# tiny_rack_v2_psu_core.net
KiCad netlist of a schematic drawn in EAGLE
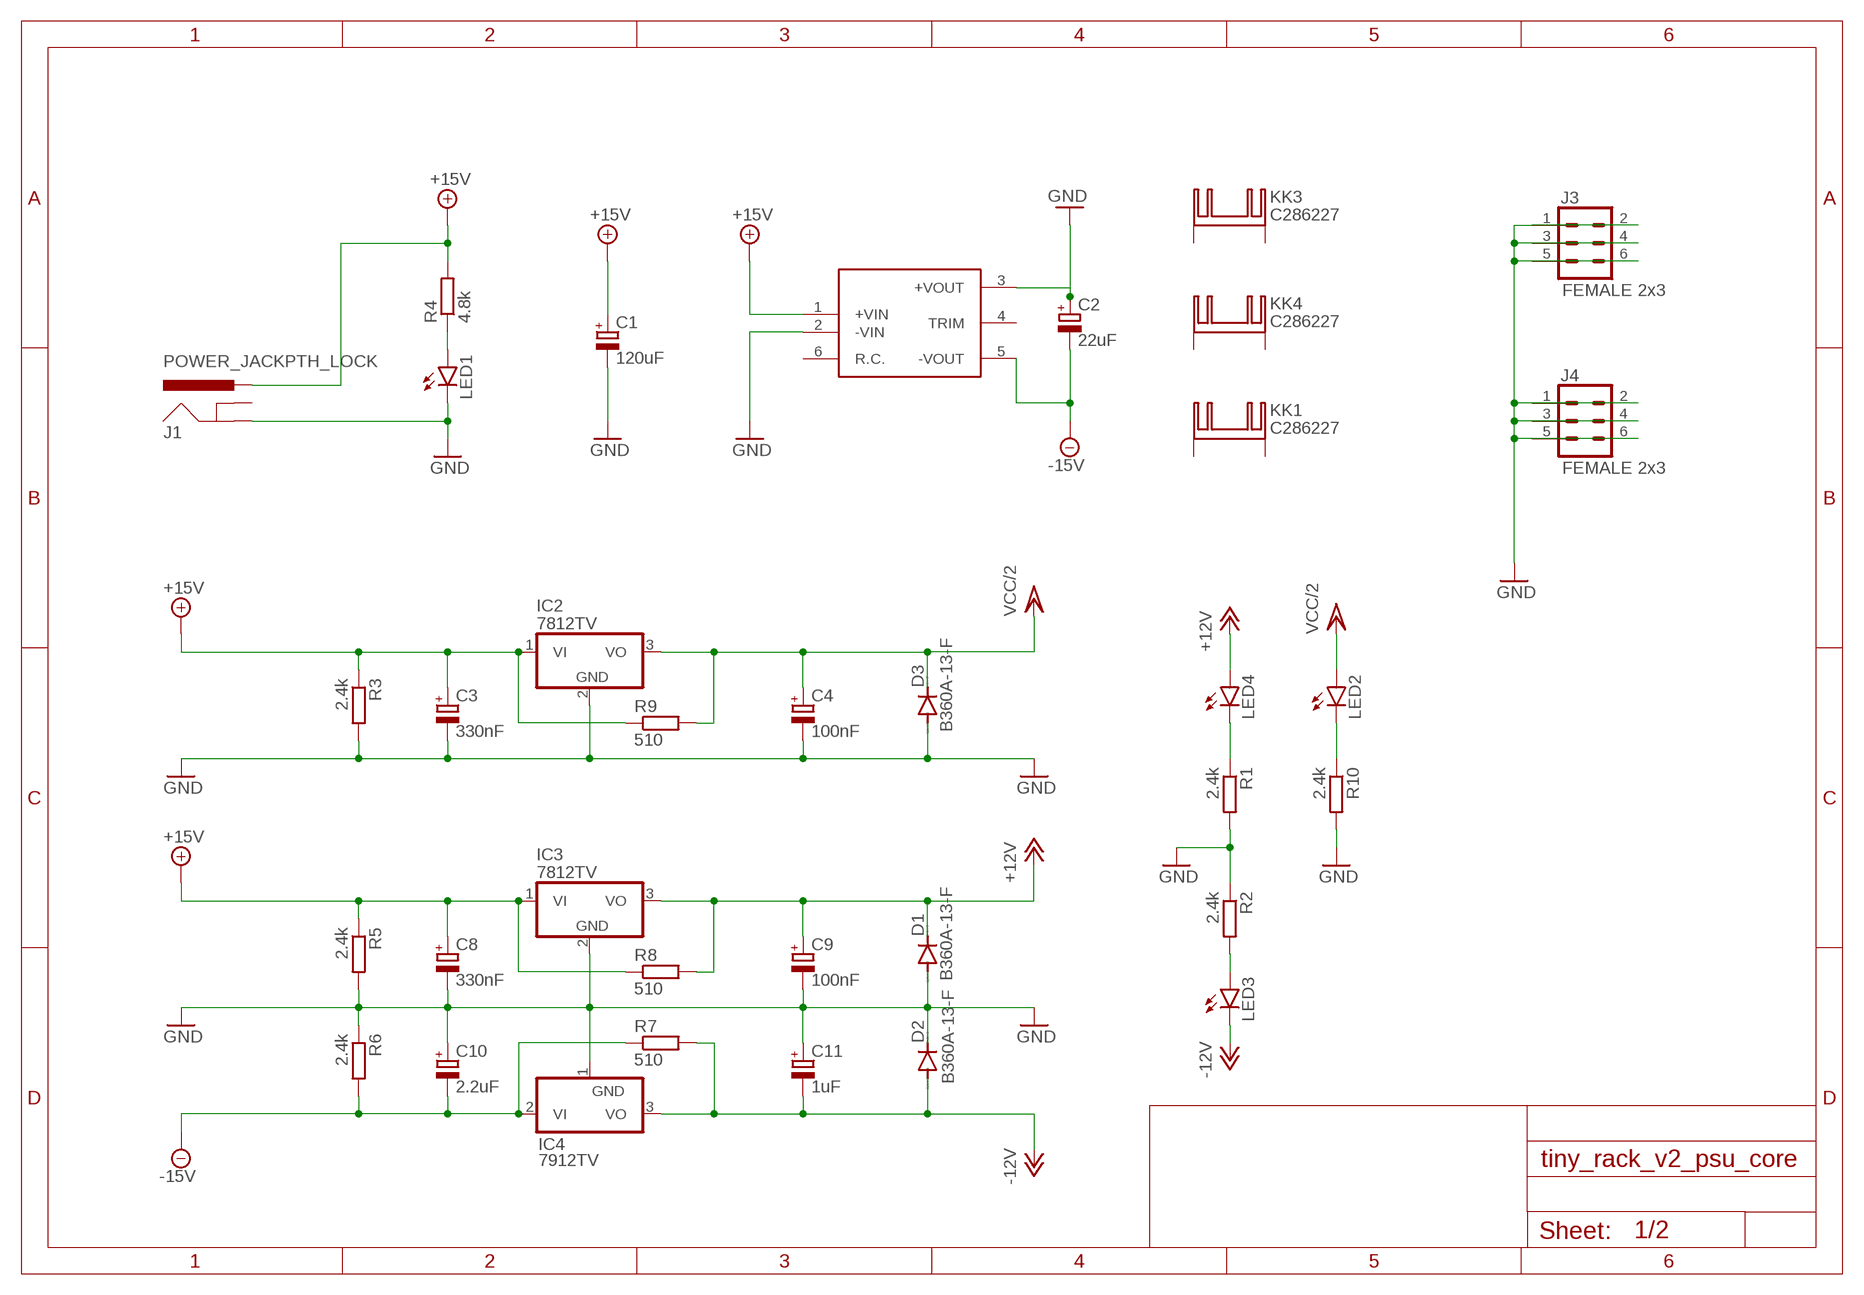
[diagram p0: schematic, sheet 1]
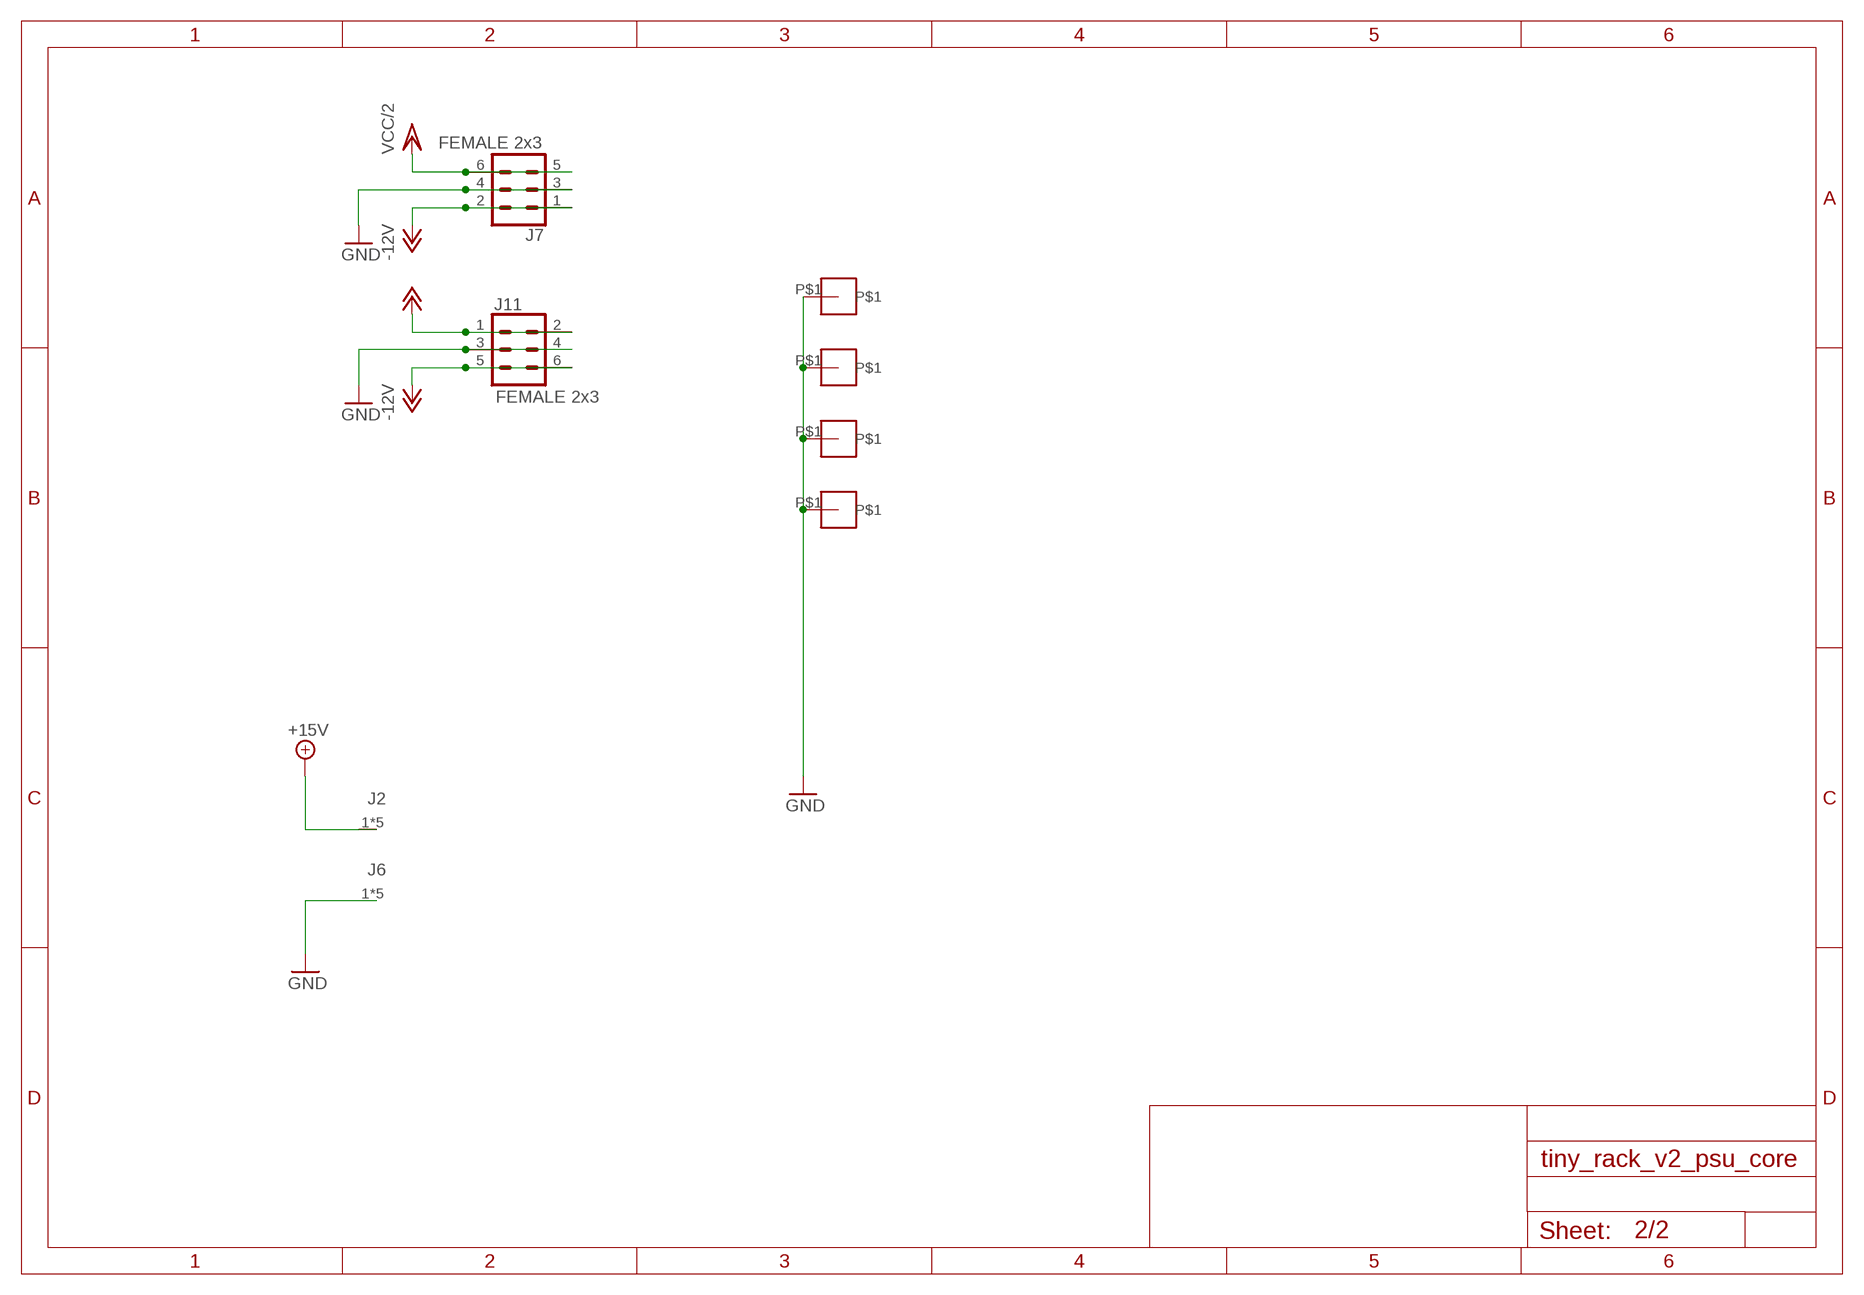
[diagram p1: schematic, sheet 2]

(export (version "E")
  (design (tool "Eeschema 10.0.6"))
  (components
    (comp (ref "J2")
      (value "30A-SCREW-CONN")
      (footprint "eagle-import:50X72")
      (libsource (lib "eagle-import") (part "30A-SCREW-CONN"))
    )
    (comp (ref "J6")
      (value "30A-SCREW-CONN")
      (footprint "eagle-import:50X72")
      (libsource (lib "eagle-import") (part "30A-SCREW-CONN"))
    )
    (comp (ref "J7")
      (value "FEMALE 2x3")
      (footprint "eagle-import:2X3")
      (libsource (lib "eagle-import") (part "CONN_03X2FEMALE"))
    )
    (comp (ref "J11")
      (value "FEMALE 2x3")
      (footprint "eagle-import:2X3")
      (libsource (lib "eagle-import") (part "CONN_03X2FEMALE"))
    )
    (comp (ref "U$3")
      (value "M3-HOLE")
      (footprint "eagle-import:M3-HOLE")
      (libsource (lib "eagle-import") (part "M3-HOLE"))
    )
    (comp (ref "U$4")
      (value "M3-HOLE")
      (footprint "eagle-import:M3-HOLE")
      (libsource (lib "eagle-import") (part "M3-HOLE"))
    )
    (comp (ref "U$5")
      (value "M3-HOLE")
      (footprint "eagle-import:M3-HOLE")
      (libsource (lib "eagle-import") (part "M3-HOLE"))
    )
    (comp (ref "U$6")
      (value "M3-HOLE")
      (footprint "eagle-import:M3-HOLE")
      (libsource (lib "eagle-import") (part "M3-HOLE"))
    )
    (comp (ref "C1")
      (value "120uF")
      (footprint "eagle-import:E5-10,5")
      (libsource (lib "eagle-import") (part "CPOL-EUE5-10.5"))
    )
    (comp (ref "C2")
      (value "22uF")
      (footprint "eagle-import:E2,5-6")
      (libsource (lib "eagle-import") (part "CPOL-EUE2.5-6"))
    )
    (comp (ref "C3")
      (value "330nF")
      (footprint "eagle-import:CAPMP3216X180N")
      (libsource (lib "eagle-import") (part "C-POLTANTALUM-1206(3216-METRIC)_"))
    )
    (comp (ref "C4")
      (value "100nF")
      (footprint "eagle-import:CAPMP3216X180N")
      (libsource (lib "eagle-import") (part "C-POLTANTALUM-1206(3216-METRIC)_"))
    )
    (comp (ref "C8")
      (value "330nF")
      (footprint "eagle-import:CAPMP3216X180N")
      (libsource (lib "eagle-import") (part "C-POLTANTALUM-1206(3216-METRIC)_"))
    )
    (comp (ref "C9")
      (value "100nF")
      (footprint "eagle-import:CAPMP3216X180N")
      (libsource (lib "eagle-import") (part "C-POLTANTALUM-1206(3216-METRIC)_"))
    )
    (comp (ref "C10")
      (value "2.2uF")
      (footprint "eagle-import:CAPMP3528X210N")
      (libsource (lib "eagle-import") (part "C-POLTANTALUM-1411(3528-METRIC)_"))
    )
    (comp (ref "C11")
      (value "1uF")
      (footprint "eagle-import:CAPMP3216X180N")
      (libsource (lib "eagle-import") (part "C-POLTANTALUM-1206(3216-METRIC)_"))
    )
    (comp (ref "D1")
      (value "B360A-13-F")
      (footprint "eagle-import:DO-214AC")
      (libsource (lib "eagle-import") (part "DIODE-DO-214AC"))
    )
    (comp (ref "D2")
      (value "B360A-13-F")
      (footprint "eagle-import:DO-214AC")
      (libsource (lib "eagle-import") (part "DIODE-DO-214AC"))
    )
    (comp (ref "D3")
      (value "B360A-13-F")
      (footprint "eagle-import:DO-214AC")
      (libsource (lib "eagle-import") (part "DIODE-DO-214AC"))
    )
    (comp (ref "IC1")
      (value "SKMW")
      (footprint "eagle-import:SKMW")
      (libsource (lib "eagle-import") (part "SKMW"))
    )
    (comp (ref "IC2")
      (value "7812TV")
      (footprint "eagle-import:TO220V")
      (libsource (lib "eagle-import") (part "78TV12"))
    )
    (comp (ref "IC3")
      (value "7812TV")
      (footprint "eagle-import:TO220V")
      (libsource (lib "eagle-import") (part "78TV12"))
    )
    (comp (ref "IC4")
      (value "7912TV")
      (footprint "eagle-import:TO220V")
      (libsource (lib "eagle-import") (part "79TV12"))
    )
    (comp (ref "J1")
      (value "POWER_JACKPTH_LOCK")
      (footprint "eagle-import:POWER_JACK_PTH_LOCK")
      (libsource (lib "eagle-import") (part "POWER_JACKPTH_LOCK"))
    )
    (comp (ref "J3")
      (value "FEMALE 2x3")
      (footprint "eagle-import:2X3")
      (libsource (lib "eagle-import") (part "CONN_03X2FEMALE"))
    )
    (comp (ref "J4")
      (value "FEMALE 2x3")
      (footprint "eagle-import:2X3")
      (libsource (lib "eagle-import") (part "CONN_03X2FEMALE"))
    )
    (comp (ref "KK1")
      (value "C286227")
      (footprint "eagle-import:C286227")
      (libsource (lib "eagle-import") (part "C286227"))
    )
    (comp (ref "KK3")
      (value "C286227")
      (footprint "eagle-import:C286227")
      (libsource (lib "eagle-import") (part "C286227"))
    )
    (comp (ref "KK4")
      (value "C286227")
      (footprint "eagle-import:C286227")
      (libsource (lib "eagle-import") (part "C286227"))
    )
    (comp (ref "LED1")
      (value "LEDCHIP-LED0805")
      (footprint "eagle-import:CHIP-LED0805")
      (libsource (lib "eagle-import") (part "LEDCHIP-LED0805"))
    )
    (comp (ref "LED2")
      (value "LEDCHIP-LED0805")
      (footprint "eagle-import:CHIP-LED0805")
      (libsource (lib "eagle-import") (part "LEDCHIP-LED0805"))
    )
    (comp (ref "LED3")
      (value "LEDCHIP-LED0805")
      (footprint "eagle-import:CHIP-LED0805")
      (libsource (lib "eagle-import") (part "LEDCHIP-LED0805"))
    )
    (comp (ref "LED4")
      (value "LEDCHIP-LED0805")
      (footprint "eagle-import:CHIP-LED0805")
      (libsource (lib "eagle-import") (part "LEDCHIP-LED0805"))
    )
    (comp (ref "R1")
      (value "2.4k")
      (footprint "eagle-import:R0805")
      (libsource (lib "eagle-import") (part "R-EU_R0805"))
    )
    (comp (ref "R2")
      (value "2.4k")
      (footprint "eagle-import:R0805")
      (libsource (lib "eagle-import") (part "R-EU_R0805"))
    )
    (comp (ref "R3")
      (value "2.4k")
      (footprint "eagle-import:R0805")
      (libsource (lib "eagle-import") (part "R-EU_R0805"))
    )
    (comp (ref "R4")
      (value "4.8k")
      (footprint "eagle-import:R0805")
      (libsource (lib "eagle-import") (part "R-EU_R0805"))
    )
    (comp (ref "R5")
      (value "2.4k")
      (footprint "eagle-import:R0805")
      (libsource (lib "eagle-import") (part "R-EU_R0805"))
    )
    (comp (ref "R6")
      (value "2.4k")
      (footprint "eagle-import:R0805")
      (libsource (lib "eagle-import") (part "R-EU_R0805"))
    )
    (comp (ref "R7")
      (value "510")
      (footprint "eagle-import:R0805")
      (libsource (lib "eagle-import") (part "R-EU_R0805"))
    )
    (comp (ref "R8")
      (value "510")
      (footprint "eagle-import:R0805")
      (libsource (lib "eagle-import") (part "R-EU_R0805"))
    )
    (comp (ref "R9")
      (value "510")
      (footprint "eagle-import:R0805")
      (libsource (lib "eagle-import") (part "R-EU_R0805"))
    )
    (comp (ref "R10")
      (value "2.4k")
      (footprint "eagle-import:R0805")
      (libsource (lib "eagle-import") (part "R-EU_R0805"))
    )
  )
  (nets
    (net (code "1") (name "+12V") (class "Default")
      (node (ref "C9") (pin "1") (pinfunction "+_1") (pintype "passive"))
      (node (ref "D1") (pin "C") (pinfunction "C_C") (pintype "passive"))
      (node (ref "IC3") (pin "3") (pinfunction "VO_3") (pintype "passive"))
      (node (ref "J11") (pin "1") (pinfunction "1_1") (pintype "bidirectional"))
      (node (ref "J11") (pin "2") (pinfunction "2_2") (pintype "bidirectional"))
      (node (ref "LED4") (pin "A") (pinfunction "A_A") (pintype "passive"))
      (node (ref "R8") (pin "2") (pinfunction "2_2") (pintype "passive"))
    )
    (net (code "2") (name "+15V") (class "Default")
      (node (ref "C1") (pin "+") (pinfunction "+_+") (pintype "passive"))
      (node (ref "C3") (pin "1") (pinfunction "+_1") (pintype "passive"))
      (node (ref "C8") (pin "1") (pinfunction "+_1") (pintype "passive"))
      (node (ref "IC1") (pin "1") (pinfunction "+VIN_1") (pintype "input"))
      (node (ref "IC2") (pin "1") (pinfunction "VI_1") (pintype "input"))
      (node (ref "IC3") (pin "1") (pinfunction "VI_1") (pintype "input"))
      (node (ref "J1") (pin "PWR") (pinfunction "PWR_PWR") (pintype "bidirectional"))
      (node (ref "J2") (pin "1") (pinfunction "2_1") (pintype "passive"))
      (node (ref "J2") (pin "2") (pinfunction "2_2") (pintype "passive"))
      (node (ref "J2") (pin "3") (pinfunction "2_3") (pintype "passive"))
      (node (ref "J2") (pin "4") (pinfunction "2_4") (pintype "passive"))
      (node (ref "J2") (pin "P$1") (pinfunction "2_P$1") (pintype "passive"))
      (node (ref "R3") (pin "1") (pinfunction "1_1") (pintype "passive"))
      (node (ref "R4") (pin "2") (pinfunction "2_2") (pintype "passive"))
      (node (ref "R5") (pin "1") (pinfunction "1_1") (pintype "passive"))
      (node (ref "R8") (pin "1") (pinfunction "1_1") (pintype "passive"))
      (node (ref "R9") (pin "1") (pinfunction "1_1") (pintype "passive"))
    )
    (net (code "3") (name "-12V") (class "Default")
      (node (ref "C11") (pin "2") (pinfunction "-_2") (pintype "passive"))
      (node (ref "D2") (pin "A") (pinfunction "A_A") (pintype "passive"))
      (node (ref "IC4") (pin "3") (pinfunction "VO_3") (pintype "passive"))
      (node (ref "J11") (pin "5") (pinfunction "5_5") (pintype "bidirectional"))
      (node (ref "J11") (pin "6") (pinfunction "6_6") (pintype "bidirectional"))
      (node (ref "J7") (pin "1") (pinfunction "1_1") (pintype "bidirectional"))
      (node (ref "J7") (pin "2") (pinfunction "2_2") (pintype "bidirectional"))
      (node (ref "LED3") (pin "C") (pinfunction "C_C") (pintype "passive"))
      (node (ref "R7") (pin "2") (pinfunction "2_2") (pintype "passive"))
    )
    (net (code "4") (name "-15V") (class "Default")
      (node (ref "C10") (pin "2") (pinfunction "-_2") (pintype "passive"))
      (node (ref "C2") (pin "-") (pinfunction "-_-") (pintype "passive"))
      (node (ref "IC1") (pin "5") (pinfunction "-VOUT_5") (pintype "output"))
      (node (ref "IC4") (pin "2") (pinfunction "VI_2") (pintype "input"))
      (node (ref "R6") (pin "2") (pinfunction "2_2") (pintype "passive"))
      (node (ref "R7") (pin "1") (pinfunction "1_1") (pintype "passive"))
    )
    (net (code "5") (name "GND") (class "Default")
      (node (ref "C1") (pin "-") (pinfunction "-_-") (pintype "passive"))
      (node (ref "C10") (pin "1") (pinfunction "+_1") (pintype "passive"))
      (node (ref "C11") (pin "1") (pinfunction "+_1") (pintype "passive"))
      (node (ref "C2") (pin "+") (pinfunction "+_+") (pintype "passive"))
      (node (ref "C3") (pin "2") (pinfunction "-_2") (pintype "passive"))
      (node (ref "C4") (pin "2") (pinfunction "-_2") (pintype "passive"))
      (node (ref "C8") (pin "2") (pinfunction "-_2") (pintype "passive"))
      (node (ref "C9") (pin "2") (pinfunction "-_2") (pintype "passive"))
      (node (ref "D1") (pin "A") (pinfunction "A_A") (pintype "passive"))
      (node (ref "D2") (pin "C") (pinfunction "C_C") (pintype "passive"))
      (node (ref "D3") (pin "A") (pinfunction "A_A") (pintype "passive"))
      (node (ref "IC1") (pin "2") (pinfunction "-VIN_2") (pintype "bidirectional"))
      (node (ref "IC1") (pin "3") (pinfunction "+VOUT_3") (pintype "output"))
      (node (ref "IC2") (pin "2") (pinfunction "GND_2") (pintype "passive"))
      (node (ref "IC3") (pin "2") (pinfunction "GND_2") (pintype "passive"))
      (node (ref "IC4") (pin "1") (pinfunction "GND_1") (pintype "passive"))
      (node (ref "J1") (pin "GND") (pinfunction "GND_GND") (pintype "bidirectional"))
      (node (ref "J11") (pin "3") (pinfunction "3_3") (pintype "bidirectional"))
      (node (ref "J11") (pin "4") (pinfunction "4_4") (pintype "bidirectional"))
      (node (ref "J3") (pin "1") (pinfunction "1_1") (pintype "bidirectional"))
      (node (ref "J3") (pin "2") (pinfunction "2_2") (pintype "bidirectional"))
      (node (ref "J3") (pin "3") (pinfunction "3_3") (pintype "bidirectional"))
      (node (ref "J3") (pin "4") (pinfunction "4_4") (pintype "bidirectional"))
      (node (ref "J3") (pin "5") (pinfunction "5_5") (pintype "bidirectional"))
      (node (ref "J3") (pin "6") (pinfunction "6_6") (pintype "bidirectional"))
      (node (ref "J4") (pin "1") (pinfunction "1_1") (pintype "bidirectional"))
      (node (ref "J4") (pin "2") (pinfunction "2_2") (pintype "bidirectional"))
      (node (ref "J4") (pin "3") (pinfunction "3_3") (pintype "bidirectional"))
      (node (ref "J4") (pin "4") (pinfunction "4_4") (pintype "bidirectional"))
      (node (ref "J4") (pin "5") (pinfunction "5_5") (pintype "bidirectional"))
      (node (ref "J4") (pin "6") (pinfunction "6_6") (pintype "bidirectional"))
      (node (ref "J6") (pin "1") (pinfunction "2_1") (pintype "passive"))
      (node (ref "J6") (pin "2") (pinfunction "2_2") (pintype "passive"))
      (node (ref "J6") (pin "3") (pinfunction "2_3") (pintype "passive"))
      (node (ref "J6") (pin "4") (pinfunction "2_4") (pintype "passive"))
      (node (ref "J6") (pin "P$1") (pinfunction "2_P$1") (pintype "passive"))
      (node (ref "J7") (pin "3") (pinfunction "3_3") (pintype "bidirectional"))
      (node (ref "J7") (pin "4") (pinfunction "4_4") (pintype "bidirectional"))
      (node (ref "LED1") (pin "C") (pinfunction "C_C") (pintype "passive"))
      (node (ref "R1") (pin "2") (pinfunction "2_2") (pintype "passive"))
      (node (ref "R10") (pin "2") (pinfunction "2_2") (pintype "passive"))
      (node (ref "R2") (pin "1") (pinfunction "1_1") (pintype "passive"))
      (node (ref "R3") (pin "2") (pinfunction "2_2") (pintype "passive"))
      (node (ref "R5") (pin "2") (pinfunction "2_2") (pintype "passive"))
      (node (ref "R6") (pin "1") (pinfunction "1_1") (pintype "passive"))
      (node (ref "U$3") (pin "P$1") (pinfunction "P$1_P$1") (pintype "bidirectional"))
      (node (ref "U$4") (pin "P$1") (pinfunction "P$1_P$1") (pintype "bidirectional"))
      (node (ref "U$5") (pin "P$1") (pinfunction "P$1_P$1") (pintype "bidirectional"))
      (node (ref "U$6") (pin "P$1") (pinfunction "P$1_P$1") (pintype "bidirectional"))
    )
    (net (code "6") (name "Net-(LED1-PadA)") (class "Default")
      (node (ref "LED1") (pin "A") (pinfunction "A_A") (pintype "passive"))
      (node (ref "R4") (pin "1") (pinfunction "1_1") (pintype "passive"))
    )
    (net (code "7") (name "Net-(LED2-PadC)") (class "Default")
      (node (ref "LED2") (pin "C") (pinfunction "C_C") (pintype "passive"))
      (node (ref "R10") (pin "1") (pinfunction "1_1") (pintype "passive"))
    )
    (net (code "8") (name "Net-(LED3-PadA)") (class "Default")
      (node (ref "LED3") (pin "A") (pinfunction "A_A") (pintype "passive"))
      (node (ref "R2") (pin "2") (pinfunction "2_2") (pintype "passive"))
    )
    (net (code "9") (name "Net-(LED4-PadC)") (class "Default")
      (node (ref "LED4") (pin "C") (pinfunction "C_C") (pintype "passive"))
      (node (ref "R1") (pin "1") (pinfunction "1_1") (pintype "passive"))
    )
    (net (code "10") (name "VCC{slash}2") (class "Default")
      (node (ref "C4") (pin "1") (pinfunction "+_1") (pintype "passive"))
      (node (ref "D3") (pin "C") (pinfunction "C_C") (pintype "passive"))
      (node (ref "IC2") (pin "3") (pinfunction "VO_3") (pintype "passive"))
      (node (ref "J7") (pin "5") (pinfunction "5_5") (pintype "bidirectional"))
      (node (ref "J7") (pin "6") (pinfunction "6_6") (pintype "bidirectional"))
      (node (ref "LED2") (pin "A") (pinfunction "A_A") (pintype "passive"))
      (node (ref "R9") (pin "2") (pinfunction "2_2") (pintype "passive"))
    )
    (net (code "11") (name "unconnected-(IC1-R.C.-Pad6)") (class "Default")
      (node (ref "IC1") (pin "6") (pinfunction "R.C._6") (pintype "input"))
    )
    (net (code "12") (name "unconnected-(IC1-TRIM-Pad4)") (class "Default")
      (node (ref "IC1") (pin "4") (pinfunction "TRIM_4") (pintype "output"))
    )
    (net (code "13") (name "unconnected-(J1-PadGNDBREAK)") (class "Default")
      (node (ref "J1") (pin "GNDBREAK") (pinfunction "GNDBREAK_GNDBREAK") (pintype "bidirectional"))
    )
    (net (code "14") (name "unconnected-(KK1-K-PadA2,2)") (class "Default")
      (node (ref "KK1") (pin "A2,2") (pinfunction "K_A2,2") (pintype "passive"))
    )
    (net (code "15") (name "unconnected-(KK1-K-PadB2,2)") (class "Default")
      (node (ref "KK1") (pin "B2,2") (pinfunction "K_B2,2") (pintype "passive"))
    )
    (net (code "16") (name "unconnected-(KK3-K-PadA2,2)") (class "Default")
      (node (ref "KK3") (pin "A2,2") (pinfunction "K_A2,2") (pintype "passive"))
    )
    (net (code "17") (name "unconnected-(KK3-K-PadB2,2)") (class "Default")
      (node (ref "KK3") (pin "B2,2") (pinfunction "K_B2,2") (pintype "passive"))
    )
    (net (code "18") (name "unconnected-(KK4-K-PadA2,2)") (class "Default")
      (node (ref "KK4") (pin "A2,2") (pinfunction "K_A2,2") (pintype "passive"))
    )
    (net (code "19") (name "unconnected-(KK4-K-PadB2,2)") (class "Default")
      (node (ref "KK4") (pin "B2,2") (pinfunction "K_B2,2") (pintype "passive"))
    )
  )
)
